# upconverter.net
KiCad netlist of a schematic drawn in EAGLE
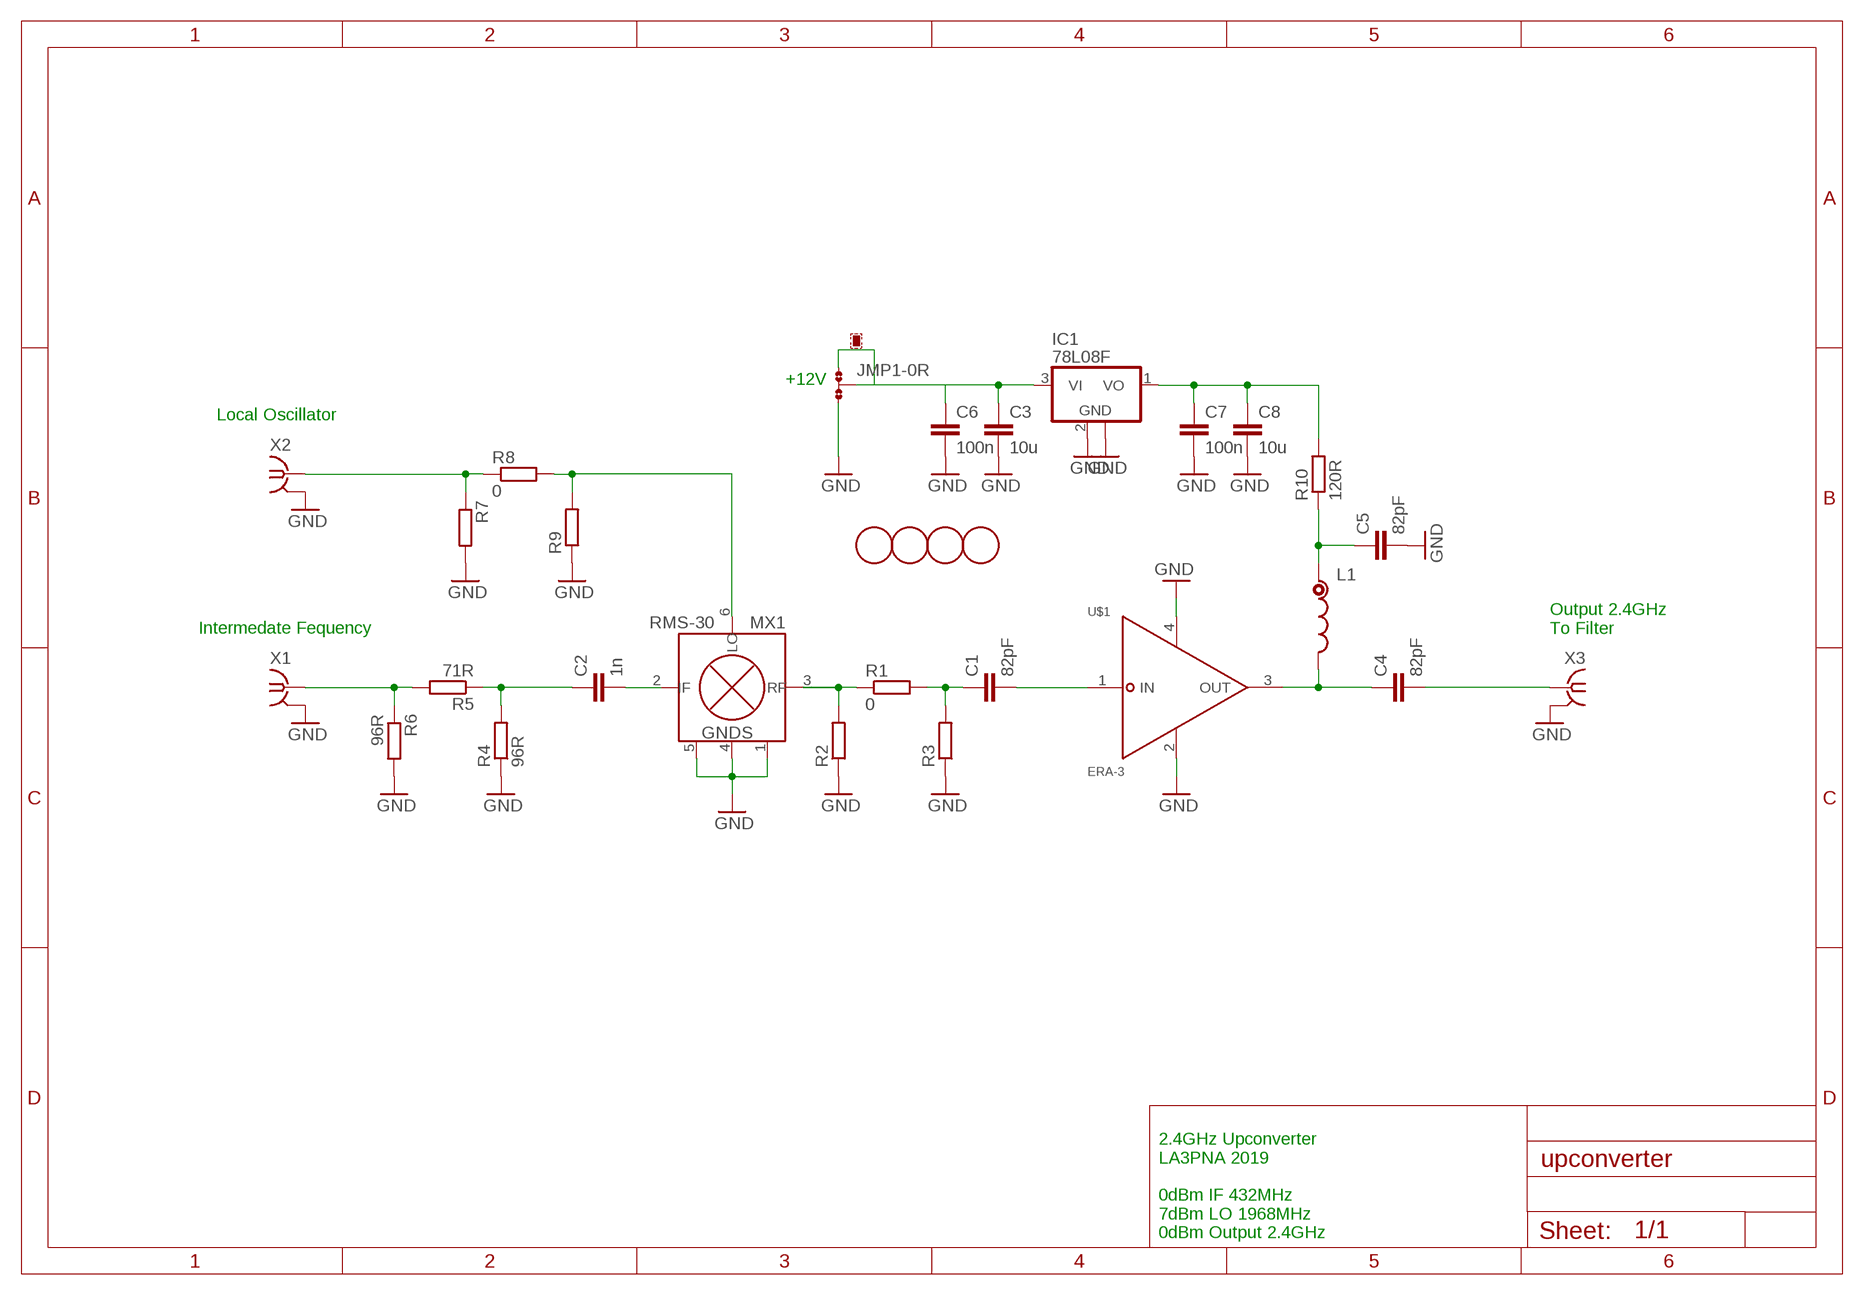
[diagram p0: schematic, sheet 1]

(export (version "E")
  (design (tool "Eeschema 10.0.6"))
  (components
    (comp (ref "C1")
      (value "82pF")
      (footprint "eagle-import:C0603K")
      (libsource (lib "eagle-import") (part "C-EUC0603K"))
    )
    (comp (ref "C2")
      (value "1n")
      (footprint "eagle-import:C0603K")
      (libsource (lib "eagle-import") (part "C-EUC0603K"))
    )
    (comp (ref "C3")
      (value "10u")
      (footprint "eagle-import:C1210")
      (libsource (lib "eagle-import") (part "C-EUC1210"))
    )
    (comp (ref "C4")
      (value "82pF")
      (footprint "eagle-import:C0805")
      (libsource (lib "eagle-import") (part "C-EUC0805"))
    )
    (comp (ref "C5")
      (value "82pF")
      (footprint "eagle-import:C0603K")
      (libsource (lib "eagle-import") (part "C-EUC0603K"))
    )
    (comp (ref "C6")
      (value "100n")
      (footprint "eagle-import:C0603K")
      (libsource (lib "eagle-import") (part "C-EUC0603K"))
    )
    (comp (ref "C7")
      (value "100n")
      (footprint "eagle-import:C0603K")
      (libsource (lib "eagle-import") (part "C-EUC0603K"))
    )
    (comp (ref "C8")
      (value "10u")
      (footprint "eagle-import:C1210")
      (libsource (lib "eagle-import") (part "C-EUC1210"))
    )
    (comp (ref "IC1")
      (value "78L08F")
      (footprint "eagle-import:SOT89")
      (libsource (lib "eagle-import") (part "78LF08"))
    )
    (comp (ref "JMP1")
      (value "0R-JUMPA")
      (footprint "eagle-import:A0R-JMP")
      (libsource (lib "eagle-import") (part "0R-JUMPA"))
    )
    (comp (ref "L1")
      (value "INDUCTOR0603")
      (footprint "eagle-import:0603")
      (libsource (lib "eagle-import") (part "INDUCTOR0603"))
    )
    (comp (ref "MX1")
      (value "RMS-30")
      (footprint "eagle-import:CD636")
      (libsource (lib "eagle-import") (part "ADE-1"))
    )
    (comp (ref "R1")
      (value "0")
      (footprint "eagle-import:R1005")
      (libsource (lib "eagle-import") (part "R-EU_R1005"))
    )
    (comp (ref "R2")
      (value "R-EU_R1005")
      (footprint "eagle-import:R1005")
      (libsource (lib "eagle-import") (part "R-EU_R1005"))
    )
    (comp (ref "R3")
      (value "R-EU_R1005")
      (footprint "eagle-import:R1005")
      (libsource (lib "eagle-import") (part "R-EU_R1005"))
    )
    (comp (ref "R4")
      (value "96R")
      (footprint "eagle-import:R1005")
      (libsource (lib "eagle-import") (part "R-EU_R1005"))
    )
    (comp (ref "R5")
      (value "71R")
      (footprint "eagle-import:R1005")
      (libsource (lib "eagle-import") (part "R-EU_R1005"))
    )
    (comp (ref "R6")
      (value "96R")
      (footprint "eagle-import:R1005")
      (libsource (lib "eagle-import") (part "R-EU_R1005"))
    )
    (comp (ref "R7")
      (value "R-EU_R1005")
      (footprint "eagle-import:R1005")
      (libsource (lib "eagle-import") (part "R-EU_R1005"))
    )
    (comp (ref "R8")
      (value "0")
      (footprint "eagle-import:R1005")
      (libsource (lib "eagle-import") (part "R-EU_R1005"))
    )
    (comp (ref "R9")
      (value "R-EU_R1005")
      (footprint "eagle-import:R1005")
      (libsource (lib "eagle-import") (part "R-EU_R1005"))
    )
    (comp (ref "R10")
      (value "120R")
      (footprint "eagle-import:R1206")
      (libsource (lib "eagle-import") (part "R-EU_R1206"))
    )
    (comp (ref "U$1")
      (value "ERA-3")
      (footprint "eagle-import:MAR4SM")
      (libsource (lib "eagle-import") (part "MAR4SM"))
    )
    (comp (ref "U$2")
      (value "FIDUCIAL")
      (footprint "eagle-import:FIDUCIAL_1MM")
      (libsource (lib "eagle-import") (part "FIDUCIAL"))
    )
    (comp (ref "U$3")
      (value "FIDUCIAL")
      (footprint "eagle-import:FIDUCIAL_1MM")
      (libsource (lib "eagle-import") (part "FIDUCIAL"))
    )
    (comp (ref "U$4")
      (value "FIDUCIAL")
      (footprint "eagle-import:FIDUCIAL_1MM")
      (libsource (lib "eagle-import") (part "FIDUCIAL"))
    )
    (comp (ref "U$5")
      (value "FIDUCIAL")
      (footprint "eagle-import:FIDUCIAL_1MM")
      (libsource (lib "eagle-import") (part "FIDUCIAL"))
    )
    (comp (ref "X1")
      (value "SMA-142-0711-821/826")
      (footprint "eagle-import:J502-ND-142-0711-821_826")
      (fields (field (name "MF") "JOHNSON COMPONENTS") (field (name "MPN") "142-0711-821"))
      (libsource (lib "eagle-import") (part "SMA-142-0711-821/826"))
    )
    (comp (ref "X2")
      (value "SMA-142-0711-821/826")
      (footprint "eagle-import:J502-ND-142-0711-821_826")
      (fields (field (name "MF") "JOHNSON COMPONENTS") (field (name "MPN") "142-0711-821"))
      (libsource (lib "eagle-import") (part "SMA-142-0711-821/826"))
    )
    (comp (ref "X3")
      (value "SMA-142-0711-821/826")
      (footprint "eagle-import:J502-ND-142-0711-821_826")
      (fields (field (name "MF") "JOHNSON COMPONENTS") (field (name "MPN") "142-0711-821"))
      (libsource (lib "eagle-import") (part "SMA-142-0711-821/826"))
    )
  )
  (nets
    (net (code "1") (name "GND") (class "Default")
      (node (ref "C3") (pin "2") (pinfunction "2_2") (pintype "passive"))
      (node (ref "C5") (pin "2") (pinfunction "2_2") (pintype "passive"))
      (node (ref "C6") (pin "2") (pinfunction "2_2") (pintype "passive"))
      (node (ref "C7") (pin "2") (pinfunction "2_2") (pintype "passive"))
      (node (ref "C8") (pin "2") (pinfunction "2_2") (pintype "passive"))
      (node (ref "IC1") (pin "2") (pinfunction "GND_2") (pintype "passive"))
      (node (ref "IC1") (pin "2@1") (pinfunction "GND_2@1") (pintype "passive"))
      (node (ref "JMP1") (pin "3") (pinfunction "3_3") (pintype "passive"))
      (node (ref "MX1") (pin "1") (pinfunction "GND_1") (pintype "passive"))
      (node (ref "MX1") (pin "4") (pinfunction "GND_4") (pintype "passive"))
      (node (ref "MX1") (pin "5") (pinfunction "GND_5") (pintype "passive"))
      (node (ref "R2") (pin "1") (pinfunction "1_1") (pintype "passive"))
      (node (ref "R3") (pin "1") (pinfunction "1_1") (pintype "passive"))
      (node (ref "R4") (pin "1") (pinfunction "1_1") (pintype "passive"))
      (node (ref "R6") (pin "2") (pinfunction "2_2") (pintype "passive"))
      (node (ref "R7") (pin "2") (pinfunction "2_2") (pintype "passive"))
      (node (ref "R9") (pin "1") (pinfunction "1_1") (pintype "passive"))
      (node (ref "U$1") (pin "2") (pintype "bidirectional"))
      (node (ref "U$1") (pin "4") (pintype "bidirectional"))
      (node (ref "X1") (pin "G@1") (pinfunction "2_G@1") (pintype "passive"))
      (node (ref "X1") (pin "G@2") (pinfunction "2_G@2") (pintype "passive"))
      (node (ref "X1") (pin "G@3") (pinfunction "2_G@3") (pintype "passive"))
      (node (ref "X1") (pin "G@4") (pinfunction "2_G@4") (pintype "passive"))
      (node (ref "X2") (pin "G@1") (pinfunction "2_G@1") (pintype "passive"))
      (node (ref "X2") (pin "G@2") (pinfunction "2_G@2") (pintype "passive"))
      (node (ref "X2") (pin "G@3") (pinfunction "2_G@3") (pintype "passive"))
      (node (ref "X2") (pin "G@4") (pinfunction "2_G@4") (pintype "passive"))
      (node (ref "X3") (pin "G@1") (pinfunction "2_G@1") (pintype "passive"))
      (node (ref "X3") (pin "G@2") (pinfunction "2_G@2") (pintype "passive"))
      (node (ref "X3") (pin "G@3") (pinfunction "2_G@3") (pintype "passive"))
      (node (ref "X3") (pin "G@4") (pinfunction "2_G@4") (pintype "passive"))
    )
    (net (code "2") (name "Net-(C1-Pad1)") (class "Default")
      (node (ref "C1") (pin "1") (pinfunction "1_1") (pintype "passive"))
      (node (ref "R1") (pin "2") (pinfunction "2_2") (pintype "passive"))
      (node (ref "R3") (pin "2") (pinfunction "2_2") (pintype "passive"))
    )
    (net (code "3") (name "Net-(C2-Pad1)") (class "Default")
      (node (ref "C2") (pin "1") (pinfunction "1_1") (pintype "passive"))
      (node (ref "R4") (pin "2") (pinfunction "2_2") (pintype "passive"))
      (node (ref "R5") (pin "1") (pinfunction "1_1") (pintype "passive"))
    )
    (net (code "4") (name "Net-(C4-Pad2)") (class "Default")
      (node (ref "C4") (pin "2") (pinfunction "2_2") (pintype "passive"))
      (node (ref "X3") (pin "1") (pinfunction "1_1") (pintype "passive"))
    )
    (net (code "5") (name "Net-(C5-Pad1)") (class "Default")
      (node (ref "C5") (pin "1") (pinfunction "1_1") (pintype "passive"))
      (node (ref "L1") (pin "1") (pinfunction "1_1") (pintype "passive"))
      (node (ref "R10") (pin "1") (pinfunction "1_1") (pintype "passive"))
    )
    (net (code "6") (name "Net-(IC1-VI)") (class "Default")
      (node (ref "C3") (pin "1") (pinfunction "1_1") (pintype "passive"))
      (node (ref "C6") (pin "1") (pinfunction "1_1") (pintype "passive"))
      (node (ref "IC1") (pin "3") (pinfunction "VI_3") (pintype "input"))
      (node (ref "JMP1") (pin "1") (pinfunction "1_1") (pintype "passive"))
      (node (ref "JMP1") (pin "2") (pinfunction "2_2") (pintype "passive"))
    )
    (net (code "7") (name "Net-(IC1-VO)") (class "Default")
      (node (ref "C7") (pin "1") (pinfunction "1_1") (pintype "passive"))
      (node (ref "C8") (pin "1") (pinfunction "1_1") (pintype "passive"))
      (node (ref "IC1") (pin "1") (pinfunction "VO_1") (pintype "passive"))
      (node (ref "R10") (pin "2") (pinfunction "2_2") (pintype "passive"))
    )
    (net (code "8") (name "Net-(MX1-IF)") (class "Default")
      (node (ref "C2") (pin "2") (pinfunction "2_2") (pintype "passive"))
      (node (ref "MX1") (pin "2") (pinfunction "IF_2") (pintype "passive"))
    )
    (net (code "9") (name "Net-(MX1-LO)") (class "Default")
      (node (ref "MX1") (pin "6") (pinfunction "LO_6") (pintype "passive"))
      (node (ref "R8") (pin "2") (pinfunction "2_2") (pintype "passive"))
      (node (ref "R9") (pin "2") (pinfunction "2_2") (pintype "passive"))
    )
    (net (code "10") (name "Net-(MX1-RF)") (class "Default")
      (node (ref "MX1") (pin "3") (pinfunction "RF_3") (pintype "passive"))
      (node (ref "R1") (pin "1") (pinfunction "1_1") (pintype "passive"))
      (node (ref "R2") (pin "2") (pinfunction "2_2") (pintype "passive"))
    )
    (net (code "11") (name "Net-(R5-Pad2)") (class "Default")
      (node (ref "R5") (pin "2") (pinfunction "2_2") (pintype "passive"))
      (node (ref "R6") (pin "1") (pinfunction "1_1") (pintype "passive"))
      (node (ref "X1") (pin "1") (pinfunction "1_1") (pintype "passive"))
    )
    (net (code "12") (name "Net-(R7-Pad1)") (class "Default")
      (node (ref "R7") (pin "1") (pinfunction "1_1") (pintype "passive"))
      (node (ref "R8") (pin "1") (pinfunction "1_1") (pintype "passive"))
      (node (ref "X2") (pin "1") (pinfunction "1_1") (pintype "passive"))
    )
    (net (code "13") (name "Net-(U$1-IN)") (class "Default")
      (node (ref "C1") (pin "2") (pinfunction "2_2") (pintype "passive"))
      (node (ref "U$1") (pin "1") (pinfunction "IN_1") (pintype "input"))
    )
    (net (code "14") (name "Net-(U$1-OUT)") (class "Default")
      (node (ref "C4") (pin "1") (pinfunction "1_1") (pintype "passive"))
      (node (ref "L1") (pin "2") (pinfunction "2_2") (pintype "passive"))
      (node (ref "U$1") (pin "3") (pinfunction "OUT_3") (pintype "bidirectional"))
    )
  )
)
